# Main_mixer.net
KiCad netlist of a schematic drawn in EAGLE
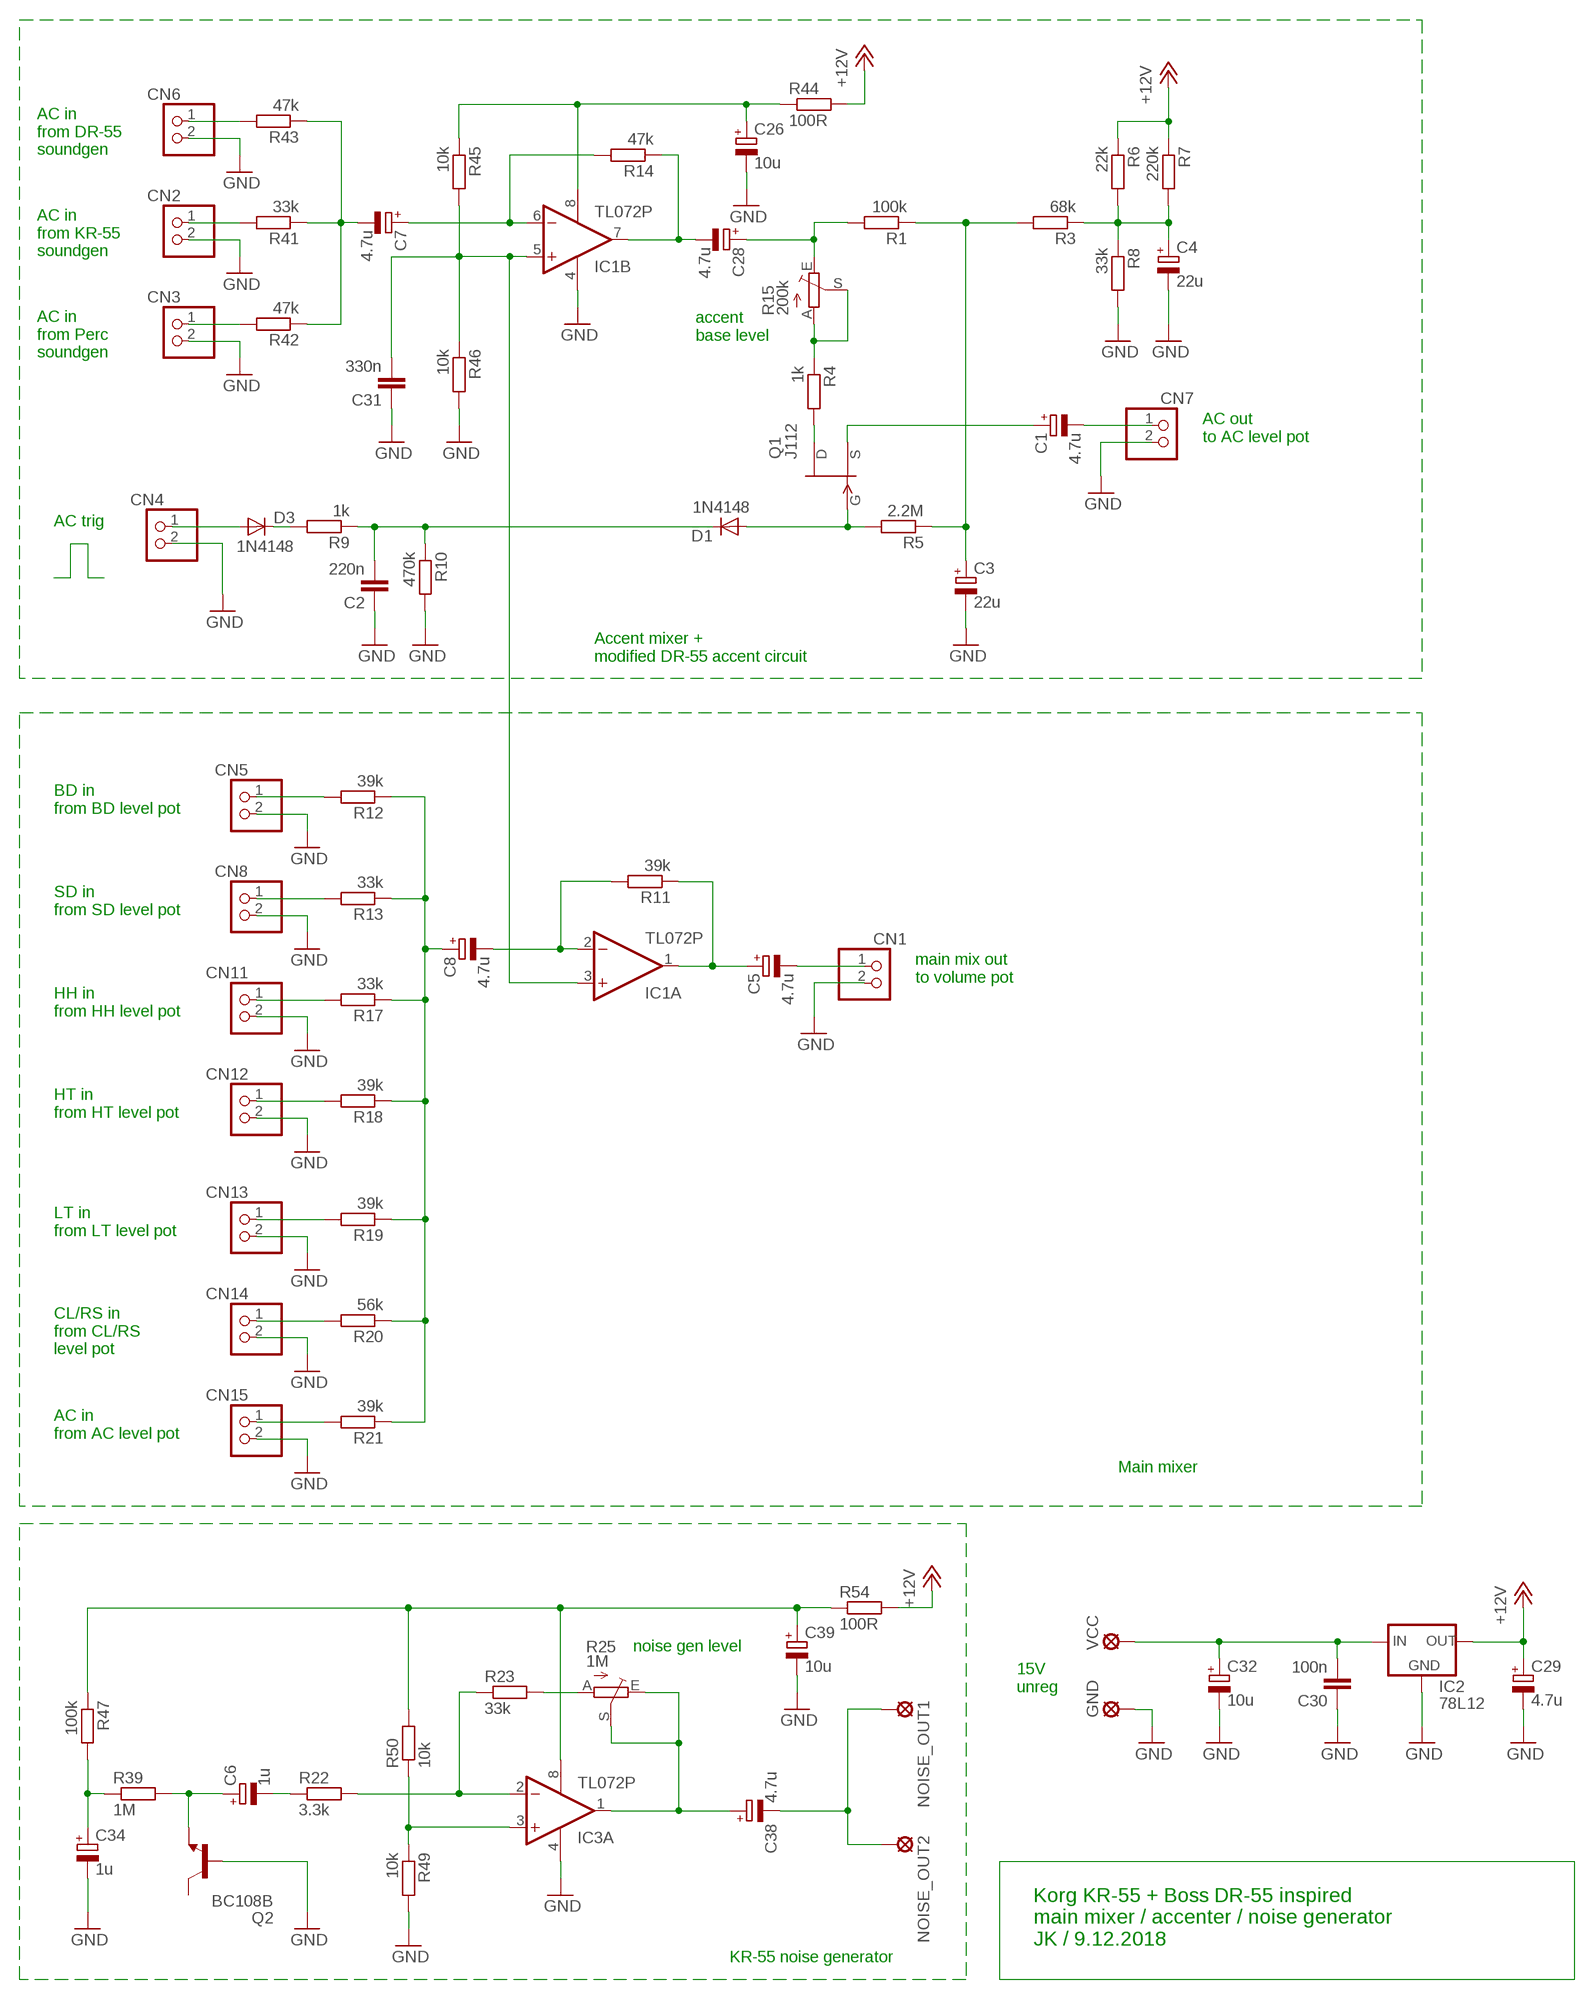
[diagram p0: schematic, sheet 1]

(export (version "E")
  (design (tool "Eeschema 10.0.6"))
  (components
    (comp (ref "C1")
      (value "4.7u")
      (footprint "eagle-import:SMC_A")
      (libsource (lib "eagle-import") (part "CPOL-EUSMCA"))
    )
    (comp (ref "C2")
      (value "220n")
      (footprint "eagle-import:C0805")
      (libsource (lib "eagle-import") (part "C-EUC0805"))
    )
    (comp (ref "C3")
      (value "22u")
      (footprint "eagle-import:E5-5")
      (libsource (lib "eagle-import") (part "CPOL-EUE5-5"))
    )
    (comp (ref "C4")
      (value "22u")
      (footprint "eagle-import:E5-5")
      (libsource (lib "eagle-import") (part "CPOL-EUE5-5"))
    )
    (comp (ref "C5")
      (value "4.7u")
      (footprint "eagle-import:SMC_A")
      (libsource (lib "eagle-import") (part "CPOL-EUSMCA"))
    )
    (comp (ref "C6")
      (value "1u")
      (footprint "eagle-import:SMC_A")
      (libsource (lib "eagle-import") (part "CPOL-EUSMCA"))
    )
    (comp (ref "C7")
      (value "4.7u")
      (footprint "eagle-import:SMC_A")
      (libsource (lib "eagle-import") (part "CPOL-EUSMCA"))
    )
    (comp (ref "C8")
      (value "4.7u")
      (footprint "eagle-import:SMC_A")
      (libsource (lib "eagle-import") (part "CPOL-EUSMCA"))
    )
    (comp (ref "C26")
      (value "10u")
      (footprint "eagle-import:E2,5-5")
      (libsource (lib "eagle-import") (part "CPOL-EUE2.5-5"))
    )
    (comp (ref "C28")
      (value "4.7u")
      (footprint "eagle-import:SMC_A")
      (libsource (lib "eagle-import") (part "CPOL-EUSMCA"))
    )
    (comp (ref "C29")
      (value "4.7u")
      (footprint "eagle-import:SMC_A")
      (libsource (lib "eagle-import") (part "CPOL-EUSMCA"))
    )
    (comp (ref "C30")
      (value "100n")
      (footprint "eagle-import:C0805")
      (libsource (lib "eagle-import") (part "C-EUC0805"))
    )
    (comp (ref "C31")
      (value "330n")
      (footprint "eagle-import:C0805")
      (libsource (lib "eagle-import") (part "C-EUC0805"))
    )
    (comp (ref "C32")
      (value "10u")
      (footprint "eagle-import:E2,5-5")
      (libsource (lib "eagle-import") (part "CPOL-EUE2.5-5"))
    )
    (comp (ref "C34")
      (value "1u")
      (footprint "eagle-import:SMC_A")
      (libsource (lib "eagle-import") (part "CPOL-EUSMCA"))
    )
    (comp (ref "C38")
      (value "4.7u")
      (footprint "eagle-import:SMC_A")
      (libsource (lib "eagle-import") (part "CPOL-EUSMCA"))
    )
    (comp (ref "C39")
      (value "10u")
      (footprint "eagle-import:E2,5-5")
      (libsource (lib "eagle-import") (part "CPOL-EUE2.5-5"))
    )
    (comp (ref "CN1")
      (value "PINHD-1X2")
      (footprint "eagle-import:1X02")
      (libsource (lib "eagle-import") (part "PINHD-1X2"))
    )
    (comp (ref "CN2")
      (value "PINHD-1X2")
      (footprint "eagle-import:1X02")
      (libsource (lib "eagle-import") (part "PINHD-1X2"))
    )
    (comp (ref "CN3")
      (value "PINHD-1X2")
      (footprint "eagle-import:1X02")
      (libsource (lib "eagle-import") (part "PINHD-1X2"))
    )
    (comp (ref "CN4")
      (value "PINHD-1X2")
      (footprint "eagle-import:1X02")
      (libsource (lib "eagle-import") (part "PINHD-1X2"))
    )
    (comp (ref "CN5")
      (value "PINHD-1X2")
      (footprint "eagle-import:1X02")
      (libsource (lib "eagle-import") (part "PINHD-1X2"))
    )
    (comp (ref "CN6")
      (value "PINHD-1X2")
      (footprint "eagle-import:1X02")
      (libsource (lib "eagle-import") (part "PINHD-1X2"))
    )
    (comp (ref "CN7")
      (value "PINHD-1X2")
      (footprint "eagle-import:1X02")
      (libsource (lib "eagle-import") (part "PINHD-1X2"))
    )
    (comp (ref "CN8")
      (value "PINHD-1X2")
      (footprint "eagle-import:1X02")
      (libsource (lib "eagle-import") (part "PINHD-1X2"))
    )
    (comp (ref "CN11")
      (value "PINHD-1X2")
      (footprint "eagle-import:1X02")
      (libsource (lib "eagle-import") (part "PINHD-1X2"))
    )
    (comp (ref "CN12")
      (value "PINHD-1X2")
      (footprint "eagle-import:1X02")
      (libsource (lib "eagle-import") (part "PINHD-1X2"))
    )
    (comp (ref "CN13")
      (value "PINHD-1X2")
      (footprint "eagle-import:1X02")
      (libsource (lib "eagle-import") (part "PINHD-1X2"))
    )
    (comp (ref "CN14")
      (value "PINHD-1X2")
      (footprint "eagle-import:1X02")
      (libsource (lib "eagle-import") (part "PINHD-1X2"))
    )
    (comp (ref "CN15")
      (value "PINHD-1X2")
      (footprint "eagle-import:1X02")
      (libsource (lib "eagle-import") (part "PINHD-1X2"))
    )
    (comp (ref "D1")
      (value "1N4148")
      (footprint "eagle-import:SOD80C")
      (libsource (lib "eagle-import") (part "DIODE-SOD80C"))
    )
    (comp (ref "D3")
      (value "1N4148")
      (footprint "eagle-import:SOD80C")
      (libsource (lib "eagle-import") (part "DIODE-SOD80C"))
    )
    (comp (ref "GND")
      (value "LSP10")
      (footprint "eagle-import:LSP10")
      (libsource (lib "eagle-import") (part "LSP10"))
    )
    (comp (ref "IC1")
      (value "TL072P")
      (footprint "eagle-import:DIL08")
      (libsource (lib "eagle-import") (part "TL072P"))
    )
    (comp (ref "IC2")
      (value "78L12")
      (footprint "eagle-import:78LXX")
      (libsource (lib "eagle-import") (part "78LXX"))
    )
    (comp (ref "IC3")
      (value "TL072P")
      (footprint "eagle-import:DIL08")
      (libsource (lib "eagle-import") (part "TL072P"))
    )
    (comp (ref "NOISE_OUT1")
      (value "LSP10")
      (footprint "eagle-import:LSP10")
      (libsource (lib "eagle-import") (part "LSP10"))
    )
    (comp (ref "NOISE_OUT2")
      (value "LSP10")
      (footprint "eagle-import:LSP10")
      (libsource (lib "eagle-import") (part "LSP10"))
    )
    (comp (ref "Q1")
      (value "J112")
      (footprint "eagle-import:TO92")
      (libsource (lib "eagle-import") (part "BF245"))
    )
    (comp (ref "Q2")
      (value "BC108B")
      (footprint "eagle-import:TO18")
      (libsource (lib "eagle-import") (part "BC108B"))
    )
    (comp (ref "R1")
      (value "100k")
      (footprint "eagle-import:R0805")
      (libsource (lib "eagle-import") (part "R-EU_R0805"))
    )
    (comp (ref "R3")
      (value "68k")
      (footprint "eagle-import:R0805")
      (libsource (lib "eagle-import") (part "R-EU_R0805"))
    )
    (comp (ref "R4")
      (value "1k")
      (footprint "eagle-import:R0805")
      (libsource (lib "eagle-import") (part "R-EU_R0805"))
    )
    (comp (ref "R5")
      (value "2.2M")
      (footprint "eagle-import:R0805")
      (libsource (lib "eagle-import") (part "R-EU_R0805"))
    )
    (comp (ref "R6")
      (value "22k")
      (footprint "eagle-import:R0805")
      (libsource (lib "eagle-import") (part "R-EU_R0805"))
    )
    (comp (ref "R7")
      (value "220k")
      (footprint "eagle-import:R0805")
      (libsource (lib "eagle-import") (part "R-EU_R0805"))
    )
    (comp (ref "R8")
      (value "33k")
      (footprint "eagle-import:R0805")
      (libsource (lib "eagle-import") (part "R-EU_R0805"))
    )
    (comp (ref "R9")
      (value "1k")
      (footprint "eagle-import:R0805")
      (libsource (lib "eagle-import") (part "R-EU_R0805"))
    )
    (comp (ref "R10")
      (value "470k")
      (footprint "eagle-import:R0805")
      (libsource (lib "eagle-import") (part "R-EU_R0805"))
    )
    (comp (ref "R11")
      (value "39k")
      (footprint "eagle-import:R0805")
      (libsource (lib "eagle-import") (part "R-EU_R0805"))
    )
    (comp (ref "R12")
      (value "39k")
      (footprint "eagle-import:R0805")
      (libsource (lib "eagle-import") (part "R-EU_R0805"))
    )
    (comp (ref "R13")
      (value "33k")
      (footprint "eagle-import:R0805")
      (libsource (lib "eagle-import") (part "R-EU_R0805"))
    )
    (comp (ref "R14")
      (value "47k")
      (footprint "eagle-import:R0805")
      (libsource (lib "eagle-import") (part "R-EU_R0805"))
    )
    (comp (ref "R15")
      (value "200k")
      (footprint "eagle-import:S63X")
      (libsource (lib "eagle-import") (part "TRIM_EU-S63X"))
    )
    (comp (ref "R17")
      (value "33k")
      (footprint "eagle-import:R0805")
      (libsource (lib "eagle-import") (part "R-EU_R0805"))
    )
    (comp (ref "R18")
      (value "39k")
      (footprint "eagle-import:R0805")
      (libsource (lib "eagle-import") (part "R-EU_R0805"))
    )
    (comp (ref "R19")
      (value "39k")
      (footprint "eagle-import:R0805")
      (libsource (lib "eagle-import") (part "R-EU_R0805"))
    )
    (comp (ref "R20")
      (value "56k")
      (footprint "eagle-import:R0805")
      (libsource (lib "eagle-import") (part "R-EU_R0805"))
    )
    (comp (ref "R21")
      (value "39k")
      (footprint "eagle-import:R0805")
      (libsource (lib "eagle-import") (part "R-EU_R0805"))
    )
    (comp (ref "R22")
      (value "3.3k")
      (footprint "eagle-import:R0805")
      (libsource (lib "eagle-import") (part "R-EU_R0805"))
    )
    (comp (ref "R23")
      (value "33k")
      (footprint "eagle-import:R0805")
      (libsource (lib "eagle-import") (part "R-EU_R0805"))
    )
    (comp (ref "R25")
      (value "1M")
      (footprint "eagle-import:S63X")
      (libsource (lib "eagle-import") (part "TRIM_EU-S63X"))
    )
    (comp (ref "R39")
      (value "1M")
      (footprint "eagle-import:R0805")
      (libsource (lib "eagle-import") (part "R-EU_R0805"))
    )
    (comp (ref "R41")
      (value "33k")
      (footprint "eagle-import:R0805")
      (libsource (lib "eagle-import") (part "R-EU_R0805"))
    )
    (comp (ref "R42")
      (value "47k")
      (footprint "eagle-import:R0805")
      (libsource (lib "eagle-import") (part "R-EU_R0805"))
    )
    (comp (ref "R43")
      (value "47k")
      (footprint "eagle-import:R0805")
      (libsource (lib "eagle-import") (part "R-EU_R0805"))
    )
    (comp (ref "R44")
      (value "100R")
      (footprint "eagle-import:R0805")
      (libsource (lib "eagle-import") (part "R-EU_R0805"))
    )
    (comp (ref "R45")
      (value "10k")
      (footprint "eagle-import:R0805")
      (libsource (lib "eagle-import") (part "R-EU_R0805"))
    )
    (comp (ref "R46")
      (value "10k")
      (footprint "eagle-import:R0805")
      (libsource (lib "eagle-import") (part "R-EU_R0805"))
    )
    (comp (ref "R47")
      (value "100k")
      (footprint "eagle-import:R0805")
      (libsource (lib "eagle-import") (part "R-EU_R0805"))
    )
    (comp (ref "R49")
      (value "10k")
      (footprint "eagle-import:R0805")
      (libsource (lib "eagle-import") (part "R-EU_R0805"))
    )
    (comp (ref "R50")
      (value "10k")
      (footprint "eagle-import:R0805")
      (libsource (lib "eagle-import") (part "R-EU_R0805"))
    )
    (comp (ref "R54")
      (value "100R")
      (footprint "eagle-import:R0805")
      (libsource (lib "eagle-import") (part "R-EU_R0805"))
    )
    (comp (ref "VCC")
      (value "LSP10")
      (footprint "eagle-import:LSP10")
      (libsource (lib "eagle-import") (part "LSP10"))
    )
  )
  (nets
    (net (code "1") (name "+12V") (class "Default")
      (node (ref "C29") (pin "+") (pinfunction "+_+") (pintype "passive"))
      (node (ref "IC2") (pin "OUT") (pinfunction "OUT_OUT") (pintype "passive"))
      (node (ref "R44") (pin "2") (pinfunction "2_2") (pintype "passive"))
      (node (ref "R54") (pin "2") (pinfunction "2_2") (pintype "passive"))
      (node (ref "R6") (pin "1") (pinfunction "1_1") (pintype "passive"))
      (node (ref "R7") (pin "1") (pinfunction "1_1") (pintype "passive"))
    )
    (net (code "2") (name "GND") (class "Default")
      (node (ref "C2") (pin "1") (pinfunction "1_1") (pintype "passive"))
      (node (ref "C26") (pin "-") (pinfunction "-_-") (pintype "passive"))
      (node (ref "C29") (pin "-") (pinfunction "-_-") (pintype "passive"))
      (node (ref "C3") (pin "-") (pinfunction "-_-") (pintype "passive"))
      (node (ref "C30") (pin "1") (pinfunction "1_1") (pintype "passive"))
      (node (ref "C31") (pin "1") (pinfunction "1_1") (pintype "passive"))
      (node (ref "C32") (pin "-") (pinfunction "-_-") (pintype "passive"))
      (node (ref "C34") (pin "-") (pinfunction "-_-") (pintype "passive"))
      (node (ref "C39") (pin "-") (pinfunction "-_-") (pintype "passive"))
      (node (ref "C4") (pin "-") (pinfunction "-_-") (pintype "passive"))
      (node (ref "CN1") (pin "2") (pinfunction "2_2") (pintype "passive"))
      (node (ref "CN11") (pin "2") (pinfunction "2_2") (pintype "passive"))
      (node (ref "CN12") (pin "2") (pinfunction "2_2") (pintype "passive"))
      (node (ref "CN13") (pin "2") (pinfunction "2_2") (pintype "passive"))
      (node (ref "CN14") (pin "2") (pinfunction "2_2") (pintype "passive"))
      (node (ref "CN15") (pin "2") (pinfunction "2_2") (pintype "passive"))
      (node (ref "CN2") (pin "2") (pinfunction "2_2") (pintype "passive"))
      (node (ref "CN3") (pin "2") (pinfunction "2_2") (pintype "passive"))
      (node (ref "CN4") (pin "2") (pinfunction "2_2") (pintype "passive"))
      (node (ref "CN5") (pin "2") (pinfunction "2_2") (pintype "passive"))
      (node (ref "CN6") (pin "2") (pinfunction "2_2") (pintype "passive"))
      (node (ref "CN7") (pin "2") (pinfunction "2_2") (pintype "passive"))
      (node (ref "CN8") (pin "2") (pinfunction "2_2") (pintype "passive"))
      (node (ref "GND") (pin "MP") (pinfunction "MP_MP") (pintype "passive"))
      (node (ref "IC1") (pin "4") (pinfunction "V-_4") (pintype "power_in"))
      (node (ref "IC2") (pin "GND") (pinfunction "GND_GND") (pintype "input"))
      (node (ref "IC3") (pin "4") (pinfunction "V-_4") (pintype "power_in"))
      (node (ref "Q2") (pin "2") (pinfunction "B_2") (pintype "passive"))
      (node (ref "R10") (pin "2") (pinfunction "2_2") (pintype "passive"))
      (node (ref "R46") (pin "2") (pinfunction "2_2") (pintype "passive"))
      (node (ref "R49") (pin "2") (pinfunction "2_2") (pintype "passive"))
      (node (ref "R8") (pin "2") (pinfunction "2_2") (pintype "passive"))
    )
    (net (code "3") (name "Net-(C1-Pad-)") (class "Default")
      (node (ref "C1") (pin "-") (pinfunction "-_-") (pintype "passive"))
      (node (ref "CN7") (pin "1") (pinfunction "1_1") (pintype "passive"))
    )
    (net (code "4") (name "Net-(C2-Pad2)") (class "Default")
      (node (ref "C2") (pin "2") (pinfunction "2_2") (pintype "passive"))
      (node (ref "D1") (pin "C") (pinfunction "C_C") (pintype "passive"))
      (node (ref "R10") (pin "1") (pinfunction "1_1") (pintype "passive"))
      (node (ref "R9") (pin "1") (pinfunction "1_1") (pintype "passive"))
    )
    (net (code "5") (name "Net-(C3-Pad+)") (class "Default")
      (node (ref "C3") (pin "+") (pinfunction "+_+") (pintype "passive"))
      (node (ref "R1") (pin "1") (pinfunction "1_1") (pintype "passive"))
      (node (ref "R3") (pin "2") (pinfunction "2_2") (pintype "passive"))
      (node (ref "R5") (pin "1") (pinfunction "1_1") (pintype "passive"))
    )
    (net (code "6") (name "Net-(C4-Pad+)") (class "Default")
      (node (ref "C4") (pin "+") (pinfunction "+_+") (pintype "passive"))
      (node (ref "R3") (pin "1") (pinfunction "1_1") (pintype "passive"))
      (node (ref "R6") (pin "2") (pinfunction "2_2") (pintype "passive"))
      (node (ref "R7") (pin "2") (pinfunction "2_2") (pintype "passive"))
      (node (ref "R8") (pin "1") (pinfunction "1_1") (pintype "passive"))
    )
    (net (code "7") (name "Net-(C5-Pad-)") (class "Default")
      (node (ref "C5") (pin "-") (pinfunction "-_-") (pintype "passive"))
      (node (ref "CN1") (pin "1") (pinfunction "1_1") (pintype "passive"))
    )
    (net (code "8") (name "Net-(C6-Pad-)") (class "Default")
      (node (ref "C6") (pin "-") (pinfunction "-_-") (pintype "passive"))
      (node (ref "R22") (pin "1") (pinfunction "1_1") (pintype "passive"))
    )
    (net (code "9") (name "Net-(C7-Pad-)") (class "Default")
      (node (ref "C7") (pin "-") (pinfunction "-_-") (pintype "passive"))
      (node (ref "R41") (pin "1") (pinfunction "1_1") (pintype "passive"))
      (node (ref "R42") (pin "1") (pinfunction "1_1") (pintype "passive"))
      (node (ref "R43") (pin "1") (pinfunction "1_1") (pintype "passive"))
    )
    (net (code "10") (name "Net-(C8-Pad+)") (class "Default")
      (node (ref "C8") (pin "+") (pinfunction "+_+") (pintype "passive"))
      (node (ref "R12") (pin "1") (pinfunction "1_1") (pintype "passive"))
      (node (ref "R13") (pin "1") (pinfunction "1_1") (pintype "passive"))
      (node (ref "R17") (pin "1") (pinfunction "1_1") (pintype "passive"))
      (node (ref "R18") (pin "1") (pinfunction "1_1") (pintype "passive"))
      (node (ref "R19") (pin "1") (pinfunction "1_1") (pintype "passive"))
      (node (ref "R20") (pin "1") (pinfunction "1_1") (pintype "passive"))
      (node (ref "R21") (pin "1") (pinfunction "1_1") (pintype "passive"))
    )
    (net (code "11") (name "Net-(C28-Pad+)") (class "Default")
      (node (ref "C28") (pin "+") (pinfunction "+_+") (pintype "passive"))
      (node (ref "R1") (pin "2") (pinfunction "2_2") (pintype "passive"))
      (node (ref "R15") (pin "E") (pinfunction "E_E") (pintype "passive"))
    )
    (net (code "12") (name "Net-(C30-Pad2)") (class "Default")
      (node (ref "C30") (pin "2") (pinfunction "2_2") (pintype "passive"))
      (node (ref "C32") (pin "+") (pinfunction "+_+") (pintype "passive"))
      (node (ref "IC2") (pin "IN") (pinfunction "IN_IN") (pintype "input"))
      (node (ref "VCC") (pin "MP") (pinfunction "MP_MP") (pintype "passive"))
    )
    (net (code "13") (name "Net-(C34-Pad+)") (class "Default")
      (node (ref "C34") (pin "+") (pinfunction "+_+") (pintype "passive"))
      (node (ref "R39") (pin "1") (pinfunction "1_1") (pintype "passive"))
      (node (ref "R47") (pin "2") (pinfunction "2_2") (pintype "passive"))
    )
    (net (code "14") (name "Net-(C38-Pad-)") (class "Default")
      (node (ref "C38") (pin "-") (pinfunction "-_-") (pintype "passive"))
      (node (ref "NOISE_OUT1") (pin "MP") (pinfunction "MP_MP") (pintype "passive"))
      (node (ref "NOISE_OUT2") (pin "MP") (pinfunction "MP_MP") (pintype "passive"))
    )
    (net (code "15") (name "Net-(CN2-Pad1)") (class "Default")
      (node (ref "CN2") (pin "1") (pinfunction "1_1") (pintype "passive"))
      (node (ref "R41") (pin "2") (pinfunction "2_2") (pintype "passive"))
    )
    (net (code "16") (name "Net-(CN3-Pad1)") (class "Default")
      (node (ref "CN3") (pin "1") (pinfunction "1_1") (pintype "passive"))
      (node (ref "R42") (pin "2") (pinfunction "2_2") (pintype "passive"))
    )
    (net (code "17") (name "Net-(CN4-Pad1)") (class "Default")
      (node (ref "CN4") (pin "1") (pinfunction "1_1") (pintype "passive"))
      (node (ref "D3") (pin "A") (pinfunction "A_A") (pintype "passive"))
    )
    (net (code "18") (name "Net-(CN5-Pad1)") (class "Default")
      (node (ref "CN5") (pin "1") (pinfunction "1_1") (pintype "passive"))
      (node (ref "R12") (pin "2") (pinfunction "2_2") (pintype "passive"))
    )
    (net (code "19") (name "Net-(CN6-Pad1)") (class "Default")
      (node (ref "CN6") (pin "1") (pinfunction "1_1") (pintype "passive"))
      (node (ref "R43") (pin "2") (pinfunction "2_2") (pintype "passive"))
    )
    (net (code "20") (name "Net-(CN8-Pad1)") (class "Default")
      (node (ref "CN8") (pin "1") (pinfunction "1_1") (pintype "passive"))
      (node (ref "R13") (pin "2") (pinfunction "2_2") (pintype "passive"))
    )
    (net (code "21") (name "Net-(CN11-Pad1)") (class "Default")
      (node (ref "CN11") (pin "1") (pinfunction "1_1") (pintype "passive"))
      (node (ref "R17") (pin "2") (pinfunction "2_2") (pintype "passive"))
    )
    (net (code "22") (name "Net-(CN12-Pad1)") (class "Default")
      (node (ref "CN12") (pin "1") (pinfunction "1_1") (pintype "passive"))
      (node (ref "R18") (pin "2") (pinfunction "2_2") (pintype "passive"))
    )
    (net (code "23") (name "Net-(CN13-Pad1)") (class "Default")
      (node (ref "CN13") (pin "1") (pinfunction "1_1") (pintype "passive"))
      (node (ref "R19") (pin "2") (pinfunction "2_2") (pintype "passive"))
    )
    (net (code "24") (name "Net-(CN14-Pad1)") (class "Default")
      (node (ref "CN14") (pin "1") (pinfunction "1_1") (pintype "passive"))
      (node (ref "R20") (pin "2") (pinfunction "2_2") (pintype "passive"))
    )
    (net (code "25") (name "Net-(CN15-Pad1)") (class "Default")
      (node (ref "CN15") (pin "1") (pinfunction "1_1") (pintype "passive"))
      (node (ref "R21") (pin "2") (pinfunction "2_2") (pintype "passive"))
    )
    (net (code "26") (name "Net-(D3-PadC)") (class "Default")
      (node (ref "D3") (pin "C") (pinfunction "C_C") (pintype "passive"))
      (node (ref "R9") (pin "2") (pinfunction "2_2") (pintype "passive"))
    )
    (net (code "27") (name "Net-(IC1A-+IN)") (class "Default")
      (node (ref "C31") (pin "2") (pinfunction "2_2") (pintype "passive"))
      (node (ref "IC1") (pin "3") (pinfunction "+IN_3") (pintype "input"))
      (node (ref "IC1") (pin "5") (pinfunction "+IN_5") (pintype "input"))
      (node (ref "R45") (pin "2") (pinfunction "2_2") (pintype "passive"))
      (node (ref "R46") (pin "1") (pinfunction "1_1") (pintype "passive"))
    )
    (net (code "28") (name "Net-(IC1A--IN)") (class "Default")
      (node (ref "C8") (pin "-") (pinfunction "-_-") (pintype "passive"))
      (node (ref "IC1") (pin "2") (pinfunction "-IN_2") (pintype "input"))
      (node (ref "R11") (pin "2") (pinfunction "2_2") (pintype "passive"))
    )
    (net (code "29") (name "Net-(IC1A-OUT)") (class "Default")
      (node (ref "C5") (pin "+") (pinfunction "+_+") (pintype "passive"))
      (node (ref "IC1") (pin "1") (pinfunction "OUT_1") (pintype "output"))
      (node (ref "R11") (pin "1") (pinfunction "1_1") (pintype "passive"))
    )
    (net (code "30") (name "Net-(IC1B--IN)") (class "Default")
      (node (ref "C7") (pin "+") (pinfunction "+_+") (pintype "passive"))
      (node (ref "IC1") (pin "6") (pinfunction "-IN_6") (pintype "input"))
      (node (ref "R14") (pin "2") (pinfunction "2_2") (pintype "passive"))
    )
    (net (code "31") (name "Net-(IC1B-OUT)") (class "Default")
      (node (ref "C28") (pin "-") (pinfunction "-_-") (pintype "passive"))
      (node (ref "IC1") (pin "7") (pinfunction "OUT_7") (pintype "output"))
      (node (ref "R14") (pin "1") (pinfunction "1_1") (pintype "passive"))
    )
    (net (code "32") (name "Net-(IC1C-V+)") (class "Default")
      (node (ref "C26") (pin "+") (pinfunction "+_+") (pintype "passive"))
      (node (ref "IC1") (pin "8") (pinfunction "V+_8") (pintype "power_in"))
      (node (ref "R44") (pin "1") (pinfunction "1_1") (pintype "passive"))
      (node (ref "R45") (pin "1") (pinfunction "1_1") (pintype "passive"))
    )
    (net (code "33") (name "Net-(IC3A-+IN)") (class "Default")
      (node (ref "IC3") (pin "3") (pinfunction "+IN_3") (pintype "input"))
      (node (ref "R49") (pin "1") (pinfunction "1_1") (pintype "passive"))
      (node (ref "R50") (pin "1") (pinfunction "1_1") (pintype "passive"))
    )
    (net (code "34") (name "Net-(IC3A--IN)") (class "Default")
      (node (ref "IC3") (pin "2") (pinfunction "-IN_2") (pintype "input"))
      (node (ref "R22") (pin "2") (pinfunction "2_2") (pintype "passive"))
      (node (ref "R23") (pin "1") (pinfunction "1_1") (pintype "passive"))
    )
    (net (code "35") (name "Net-(IC3A-OUT)") (class "Default")
      (node (ref "C38") (pin "+") (pinfunction "+_+") (pintype "passive"))
      (node (ref "IC3") (pin "1") (pinfunction "OUT_1") (pintype "output"))
      (node (ref "R25") (pin "E") (pinfunction "E_E") (pintype "passive"))
      (node (ref "R25") (pin "S") (pinfunction "S_S") (pintype "passive"))
    )
    (net (code "36") (name "Net-(IC3C-V+)") (class "Default")
      (node (ref "C39") (pin "+") (pinfunction "+_+") (pintype "passive"))
      (node (ref "IC3") (pin "8") (pinfunction "V+_8") (pintype "power_in"))
      (node (ref "R47") (pin "1") (pinfunction "1_1") (pintype "passive"))
      (node (ref "R50") (pin "2") (pinfunction "2_2") (pintype "passive"))
      (node (ref "R54") (pin "1") (pinfunction "1_1") (pintype "passive"))
    )
    (net (code "37") (name "Net-(Q1-D)") (class "Default")
      (node (ref "Q1") (pin "1") (pinfunction "D_1") (pintype "passive"))
      (node (ref "R4") (pin "2") (pinfunction "2_2") (pintype "passive"))
    )
    (net (code "38") (name "Net-(Q1-G)") (class "Default")
      (node (ref "D1") (pin "A") (pinfunction "A_A") (pintype "passive"))
      (node (ref "Q1") (pin "3") (pinfunction "G_3") (pintype "passive"))
      (node (ref "R5") (pin "2") (pinfunction "2_2") (pintype "passive"))
    )
    (net (code "39") (name "Net-(Q1-S)") (class "Default")
      (node (ref "C1") (pin "+") (pinfunction "+_+") (pintype "passive"))
      (node (ref "Q1") (pin "2") (pinfunction "S_2") (pintype "passive"))
    )
    (net (code "40") (name "Net-(Q2-E)") (class "Default")
      (node (ref "C6") (pin "+") (pinfunction "+_+") (pintype "passive"))
      (node (ref "Q2") (pin "1") (pinfunction "E_1") (pintype "passive"))
      (node (ref "R39") (pin "2") (pinfunction "2_2") (pintype "passive"))
    )
    (net (code "41") (name "Net-(R15-PadA)") (class "Default")
      (node (ref "R15") (pin "A") (pinfunction "A_A") (pintype "passive"))
      (node (ref "R15") (pin "S") (pinfunction "S_S") (pintype "passive"))
      (node (ref "R4") (pin "1") (pinfunction "1_1") (pintype "passive"))
    )
    (net (code "42") (name "Net-(R23-Pad2)") (class "Default")
      (node (ref "R23") (pin "2") (pinfunction "2_2") (pintype "passive"))
      (node (ref "R25") (pin "A") (pinfunction "A_A") (pintype "passive"))
    )
    (net (code "43") (name "unconnected-(Q2-C-Pad3)") (class "Default")
      (node (ref "Q2") (pin "3") (pinfunction "C_3") (pintype "passive"))
    )
  )
)
